# Macro_Pad.net
KiCad netlist of a schematic drawn in EasyEDA Pro
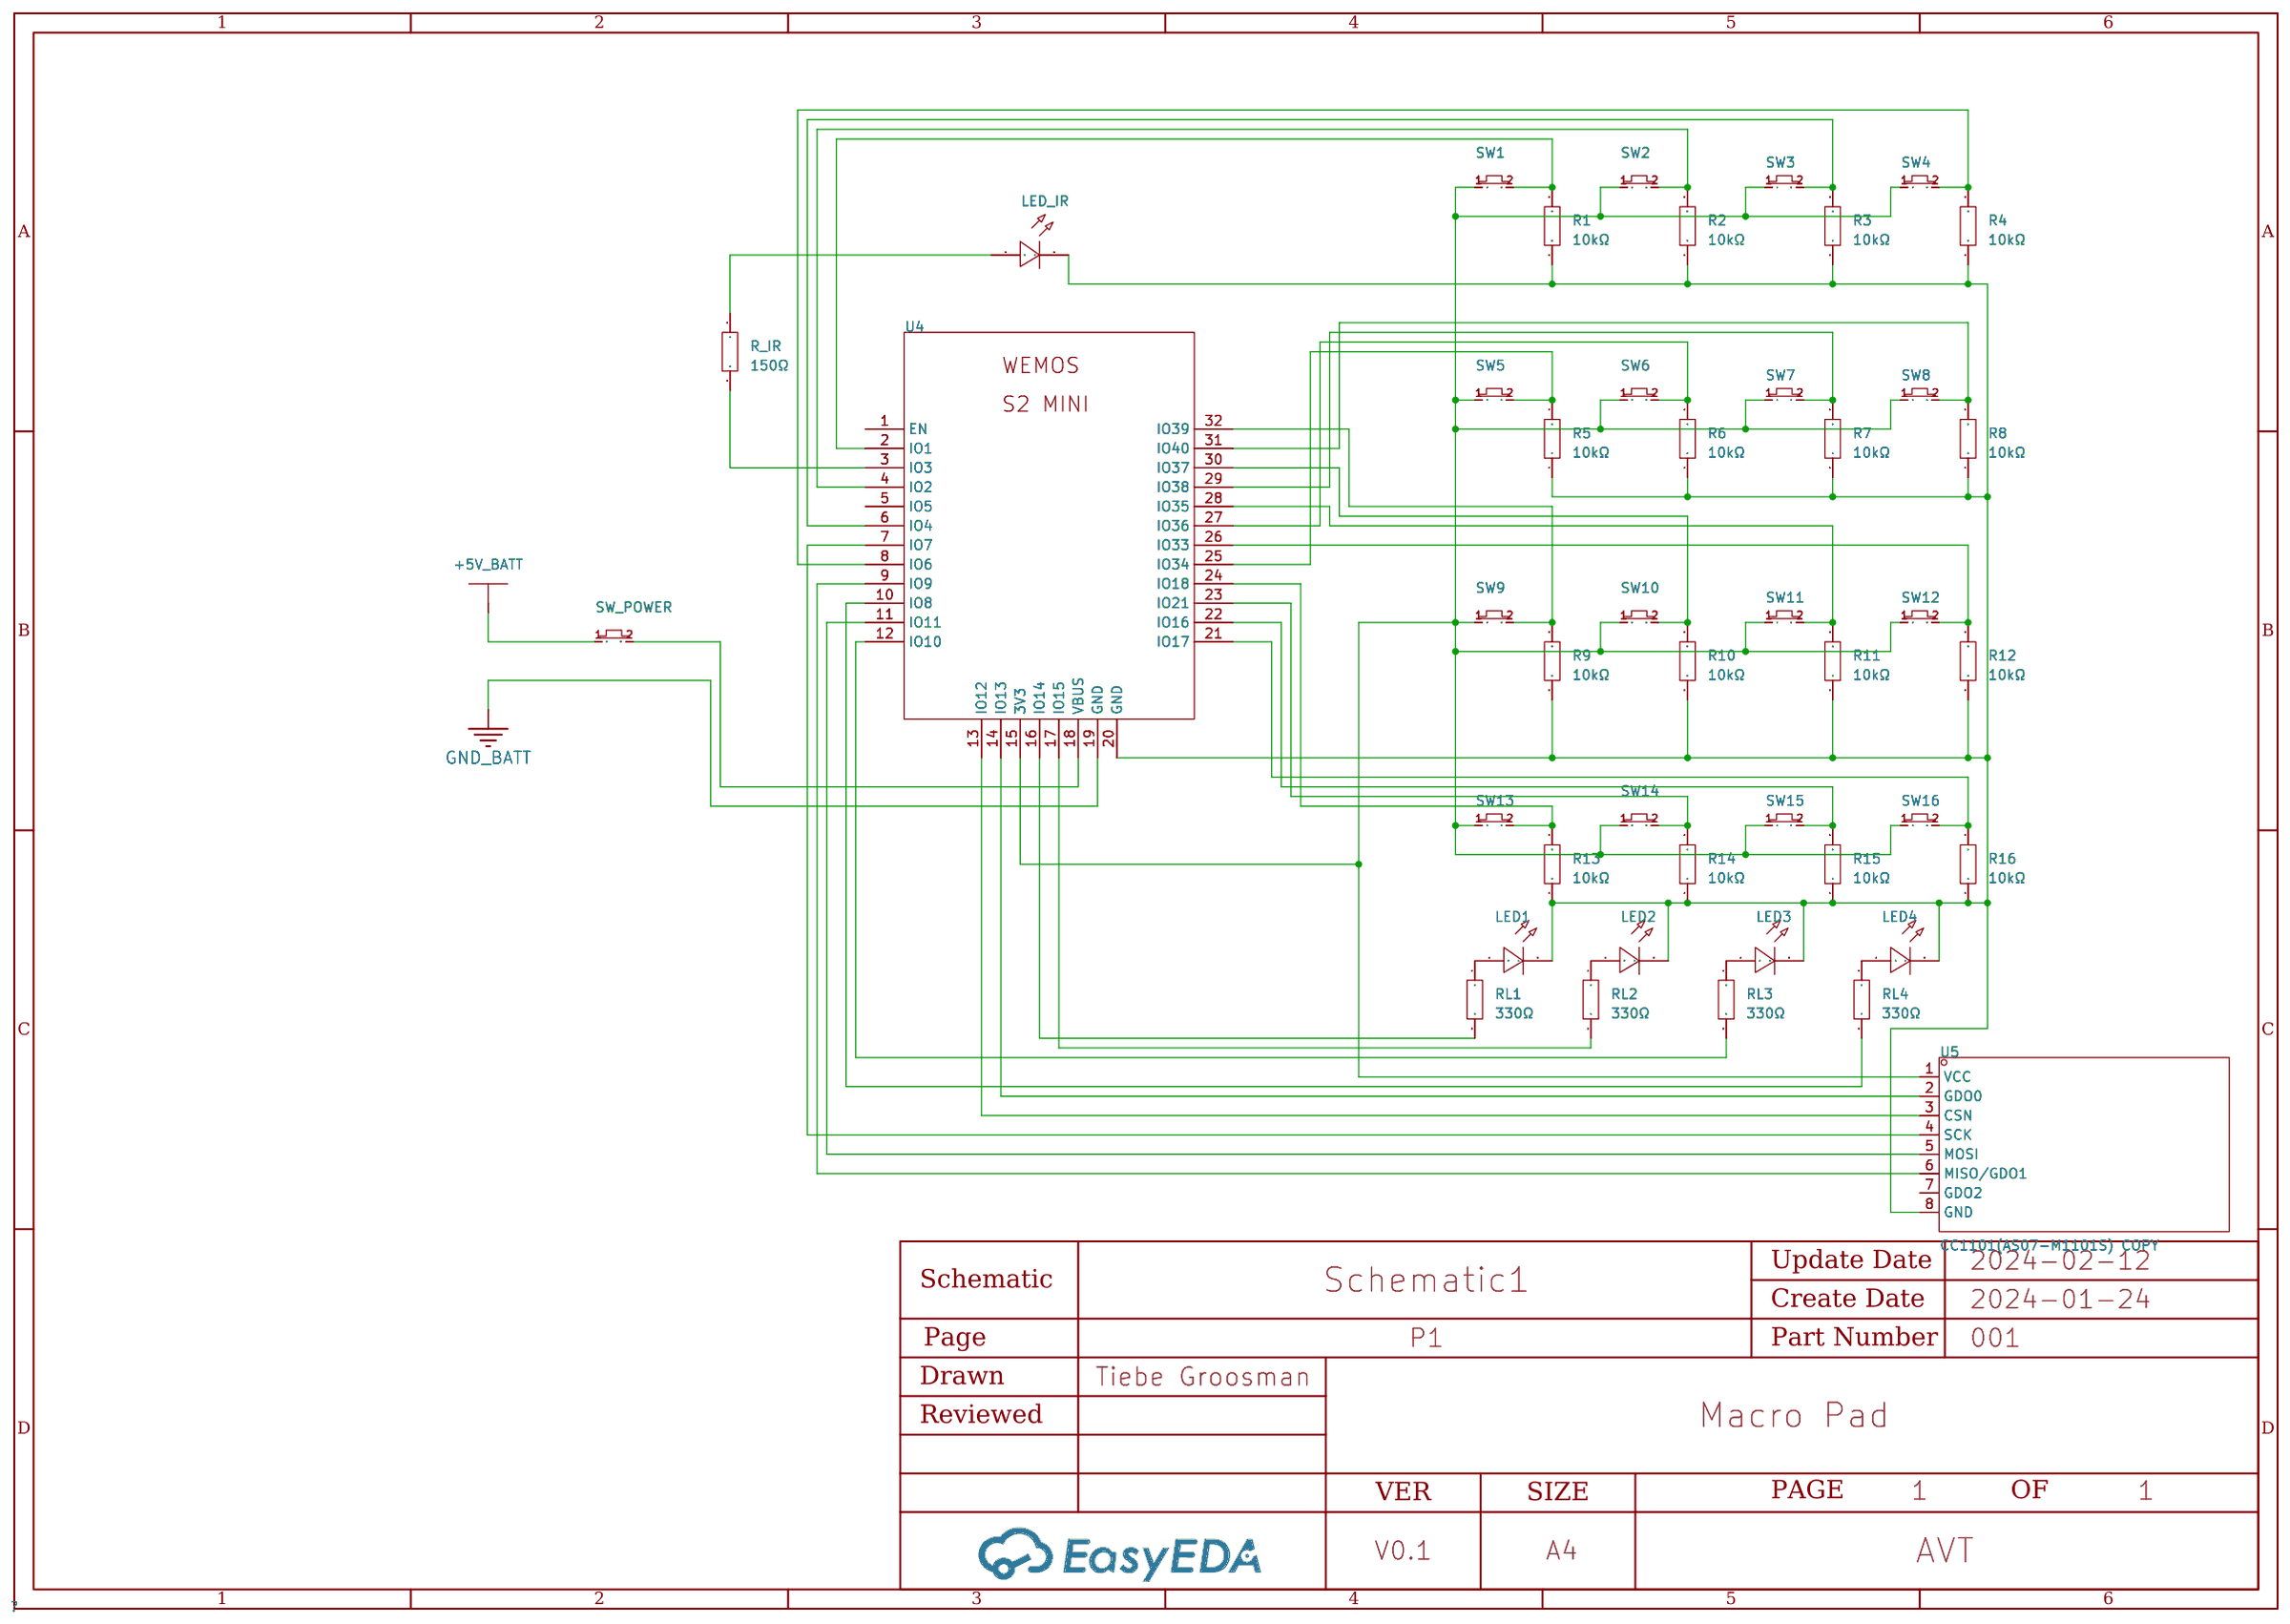
[diagram p0: schematic sheet]

(export (version "E")
  (design (tool "Eeschema 10.0.6"))
  (components
    (comp (ref "LED1")
      (value "~")
      (footprint "easyedapro:LED-TH_BD3.0-P2.54-FD")
      (libsource (lib "easyedapro") (part "LED_TH-R"))
    )
    (comp (ref "LED2")
      (value "~")
      (footprint "easyedapro:LED-TH_BD3.0-P2.54-FD")
      (libsource (lib "easyedapro") (part "LED_TH-R"))
    )
    (comp (ref "LED3")
      (value "~")
      (footprint "easyedapro:LED-TH_BD3.0-P2.54-FD")
      (libsource (lib "easyedapro") (part "LED_TH-R"))
    )
    (comp (ref "LED4")
      (value "~")
      (footprint "easyedapro:LED-TH_BD3.0-P2.54-FD")
      (libsource (lib "easyedapro") (part "LED_TH-R"))
    )
    (comp (ref "LED_IR")
      (value "~")
      (footprint "easyedapro:LED-TH_BD3.0-P2.54-FD")
      (libsource (lib "easyedapro") (part "LED_TH-R"))
    )
    (comp (ref "R1")
      (value "10kΩ")
      (footprint "easyedapro:R0201")
      (libsource (lib "easyedapro") (part "Res"))
    )
    (comp (ref "R2")
      (value "10kΩ")
      (footprint "easyedapro:R0201")
      (libsource (lib "easyedapro") (part "Res"))
    )
    (comp (ref "R3")
      (value "10kΩ")
      (footprint "easyedapro:R0201")
      (libsource (lib "easyedapro") (part "Res"))
    )
    (comp (ref "R4")
      (value "10kΩ")
      (footprint "easyedapro:R0201")
      (libsource (lib "easyedapro") (part "Res"))
    )
    (comp (ref "R5")
      (value "10kΩ")
      (footprint "easyedapro:R0201")
      (libsource (lib "easyedapro") (part "Res"))
    )
    (comp (ref "R6")
      (value "10kΩ")
      (footprint "easyedapro:R0201")
      (libsource (lib "easyedapro") (part "Res"))
    )
    (comp (ref "R7")
      (value "10kΩ")
      (footprint "easyedapro:R0201")
      (libsource (lib "easyedapro") (part "Res"))
    )
    (comp (ref "R8")
      (value "10kΩ")
      (footprint "easyedapro:R0201")
      (libsource (lib "easyedapro") (part "Res"))
    )
    (comp (ref "R9")
      (value "10kΩ")
      (footprint "easyedapro:R0201")
      (libsource (lib "easyedapro") (part "Res"))
    )
    (comp (ref "R10")
      (value "10kΩ")
      (footprint "easyedapro:R0201")
      (libsource (lib "easyedapro") (part "Res"))
    )
    (comp (ref "R11")
      (value "10kΩ")
      (footprint "easyedapro:R0201")
      (libsource (lib "easyedapro") (part "Res"))
    )
    (comp (ref "R12")
      (value "10kΩ")
      (footprint "easyedapro:R0201")
      (libsource (lib "easyedapro") (part "Res"))
    )
    (comp (ref "R13")
      (value "10kΩ")
      (footprint "easyedapro:R0201")
      (libsource (lib "easyedapro") (part "Res"))
    )
    (comp (ref "R14")
      (value "10kΩ")
      (footprint "easyedapro:R0201")
      (libsource (lib "easyedapro") (part "Res"))
    )
    (comp (ref "R15")
      (value "10kΩ")
      (footprint "easyedapro:R0201")
      (libsource (lib "easyedapro") (part "Res"))
    )
    (comp (ref "R16")
      (value "10kΩ")
      (footprint "easyedapro:R0201")
      (libsource (lib "easyedapro") (part "Res"))
    )
    (comp (ref "RL1")
      (value "330Ω")
      (footprint "easyedapro:R0201")
      (libsource (lib "easyedapro") (part "Res"))
    )
    (comp (ref "RL2")
      (value "330Ω")
      (footprint "easyedapro:R0201")
      (libsource (lib "easyedapro") (part "Res"))
    )
    (comp (ref "RL3")
      (value "330Ω")
      (footprint "easyedapro:R0201")
      (libsource (lib "easyedapro") (part "Res"))
    )
    (comp (ref "RL4")
      (value "330Ω")
      (footprint "easyedapro:R0201")
      (libsource (lib "easyedapro") (part "Res"))
    )
    (comp (ref "R_IR")
      (value "150Ω")
      (footprint "easyedapro:R0201")
      (libsource (lib "easyedapro") (part "Res"))
    )
    (comp (ref "SW1")
      (value "BUTTON-2PIN COPY")
      (footprint "easyedapro:BUTTON-2PIN")
      (fields
        (field (name "Manufacturer Part") "Switch,6*6*6Plastic head,260G, 0.25mm,Straight line")
        (field (name "Manufacturer") "BBJ")
      )
      (libsource (lib "easyedapro") (part "BUTTON-2PIN COPY"))
    )
    (comp (ref "SW2")
      (value "BUTTON-2PIN COPY")
      (footprint "easyedapro:BUTTON-2PIN")
      (fields
        (field (name "Manufacturer Part") "Switch,6*6*6Plastic head,260G, 0.25mm,Straight line")
        (field (name "Manufacturer") "BBJ")
      )
      (libsource (lib "easyedapro") (part "BUTTON-2PIN COPY"))
    )
    (comp (ref "SW3")
      (value "BUTTON-2PIN COPY")
      (footprint "easyedapro:BUTTON-2PIN")
      (fields
        (field (name "Manufacturer Part") "Switch,6*6*6Plastic head,260G, 0.25mm,Straight line")
        (field (name "Manufacturer") "BBJ")
      )
      (libsource (lib "easyedapro") (part "BUTTON-2PIN COPY"))
    )
    (comp (ref "SW4")
      (value "BUTTON-2PIN COPY")
      (footprint "easyedapro:BUTTON-2PIN")
      (fields
        (field (name "Manufacturer Part") "Switch,6*6*6Plastic head,260G, 0.25mm,Straight line")
        (field (name "Manufacturer") "BBJ")
      )
      (libsource (lib "easyedapro") (part "BUTTON-2PIN COPY"))
    )
    (comp (ref "SW5")
      (value "BUTTON-2PIN COPY")
      (footprint "easyedapro:BUTTON-2PIN")
      (fields
        (field (name "Manufacturer Part") "Switch,6*6*6Plastic head,260G, 0.25mm,Straight line")
        (field (name "Manufacturer") "BBJ")
      )
      (libsource (lib "easyedapro") (part "BUTTON-2PIN COPY"))
    )
    (comp (ref "SW6")
      (value "BUTTON-2PIN COPY")
      (footprint "easyedapro:BUTTON-2PIN")
      (fields
        (field (name "Manufacturer Part") "Switch,6*6*6Plastic head,260G, 0.25mm,Straight line")
        (field (name "Manufacturer") "BBJ")
      )
      (libsource (lib "easyedapro") (part "BUTTON-2PIN COPY"))
    )
    (comp (ref "SW7")
      (value "BUTTON-2PIN COPY")
      (footprint "easyedapro:BUTTON-2PIN")
      (fields
        (field (name "Manufacturer Part") "Switch,6*6*6Plastic head,260G, 0.25mm,Straight line")
        (field (name "Manufacturer") "BBJ")
      )
      (libsource (lib "easyedapro") (part "BUTTON-2PIN COPY"))
    )
    (comp (ref "SW8")
      (value "BUTTON-2PIN COPY")
      (footprint "easyedapro:BUTTON-2PIN")
      (fields
        (field (name "Manufacturer Part") "Switch,6*6*6Plastic head,260G, 0.25mm,Straight line")
        (field (name "Manufacturer") "BBJ")
      )
      (libsource (lib "easyedapro") (part "BUTTON-2PIN COPY"))
    )
    (comp (ref "SW9")
      (value "BUTTON-2PIN COPY")
      (footprint "easyedapro:BUTTON-2PIN")
      (fields
        (field (name "Manufacturer Part") "Switch,6*6*6Plastic head,260G, 0.25mm,Straight line")
        (field (name "Manufacturer") "BBJ")
      )
      (libsource (lib "easyedapro") (part "BUTTON-2PIN COPY"))
    )
    (comp (ref "SW10")
      (value "BUTTON-2PIN COPY")
      (footprint "easyedapro:BUTTON-2PIN")
      (fields
        (field (name "Manufacturer Part") "Switch,6*6*6Plastic head,260G, 0.25mm,Straight line")
        (field (name "Manufacturer") "BBJ")
      )
      (libsource (lib "easyedapro") (part "BUTTON-2PIN COPY"))
    )
    (comp (ref "SW11")
      (value "BUTTON-2PIN COPY")
      (footprint "easyedapro:BUTTON-2PIN")
      (fields
        (field (name "Manufacturer Part") "Switch,6*6*6Plastic head,260G, 0.25mm,Straight line")
        (field (name "Manufacturer") "BBJ")
      )
      (libsource (lib "easyedapro") (part "BUTTON-2PIN COPY"))
    )
    (comp (ref "SW12")
      (value "BUTTON-2PIN COPY")
      (footprint "easyedapro:BUTTON-2PIN")
      (fields
        (field (name "Manufacturer Part") "Switch,6*6*6Plastic head,260G, 0.25mm,Straight line")
        (field (name "Manufacturer") "BBJ")
      )
      (libsource (lib "easyedapro") (part "BUTTON-2PIN COPY"))
    )
    (comp (ref "SW13")
      (value "BUTTON-2PIN COPY")
      (footprint "easyedapro:BUTTON-2PIN")
      (fields
        (field (name "Manufacturer Part") "Switch,6*6*6Plastic head,260G, 0.25mm,Straight line")
        (field (name "Manufacturer") "BBJ")
      )
      (libsource (lib "easyedapro") (part "BUTTON-2PIN COPY"))
    )
    (comp (ref "SW14")
      (value "BUTTON-2PIN COPY")
      (footprint "easyedapro:BUTTON-2PIN")
      (fields
        (field (name "Manufacturer Part") "Switch,6*6*6Plastic head,260G, 0.25mm,Straight line")
        (field (name "Manufacturer") "BBJ")
      )
      (libsource (lib "easyedapro") (part "BUTTON-2PIN COPY"))
    )
    (comp (ref "SW15")
      (value "BUTTON-2PIN COPY")
      (footprint "easyedapro:BUTTON-2PIN")
      (fields
        (field (name "Manufacturer Part") "Switch,6*6*6Plastic head,260G, 0.25mm,Straight line")
        (field (name "Manufacturer") "BBJ")
      )
      (libsource (lib "easyedapro") (part "BUTTON-2PIN COPY"))
    )
    (comp (ref "SW16")
      (value "BUTTON-2PIN COPY")
      (footprint "easyedapro:BUTTON-2PIN")
      (fields
        (field (name "Manufacturer Part") "Switch,6*6*6Plastic head,260G, 0.25mm,Straight line")
        (field (name "Manufacturer") "BBJ")
      )
      (libsource (lib "easyedapro") (part "BUTTON-2PIN COPY"))
    )
    (comp (ref "SW_POWER")
      (value "BUTTON-2PIN COPY")
      (footprint "easyedapro:BUTTON-2PIN")
      (fields
        (field (name "Manufacturer Part") "Switch,6*6*6Plastic head,260G, 0.25mm,Straight line")
        (field (name "Manufacturer") "BBJ")
      )
      (libsource (lib "easyedapro") (part "BUTTON-2PIN COPY"))
    )
    (comp (ref "U4")
      (value "WEMOS S2 MINI COPY")
      (footprint "easyedapro:WEMOS-S2-MINI")
      (fields (field (name "Manufacturer Part") "Wemos") (field (name "Manufacturer") "WEMOS"))
      (libsource (lib "easyedapro") (part "WEMOS S2 MINI COPY"))
    )
    (comp (ref "U5")
      (value "CC1101(AS07-M1101S) COPY")
      (footprint "easyedapro:CC1101(AS07-M1101S)")
      (libsource (lib "easyedapro") (part "CC1101(AS07-M1101S) COPY"))
    )
  )
  (nets
    (net (code "1") (name "+5V_BATT") (class "Default")
      (node (ref "SW_POWER") (pin "1") (pinfunction "1_1") (pintype "input"))
    )
    (net (code "2") (name "GND_BATT") (class "Default")
      (node (ref "U4") (pin "19") (pinfunction "GND_19") (pintype "unspecified"))
    )
    (net (code "3") (name "Net-(LED1-A)") (class "Default")
      (node (ref "LED1") (pin "2") (pinfunction "A_2") (pintype "input"))
      (node (ref "LED2") (pin "2") (pinfunction "A_2") (pintype "input"))
      (node (ref "LED3") (pin "2") (pinfunction "A_2") (pintype "input"))
      (node (ref "LED4") (pin "2") (pinfunction "A_2") (pintype "input"))
      (node (ref "LED_IR") (pin "2") (pinfunction "A_2") (pintype "input"))
      (node (ref "R1") (pin "1") (pinfunction "1_1") (pintype "input"))
      (node (ref "R10") (pin "1") (pinfunction "1_1") (pintype "input"))
      (node (ref "R11") (pin "1") (pinfunction "1_1") (pintype "input"))
      (node (ref "R12") (pin "1") (pinfunction "1_1") (pintype "input"))
      (node (ref "R13") (pin "1") (pinfunction "1_1") (pintype "input"))
      (node (ref "R14") (pin "1") (pinfunction "1_1") (pintype "input"))
      (node (ref "R15") (pin "1") (pinfunction "1_1") (pintype "input"))
      (node (ref "R16") (pin "1") (pinfunction "1_1") (pintype "input"))
      (node (ref "R2") (pin "1") (pinfunction "1_1") (pintype "input"))
      (node (ref "R3") (pin "1") (pinfunction "1_1") (pintype "input"))
      (node (ref "R4") (pin "1") (pinfunction "1_1") (pintype "input"))
      (node (ref "R5") (pin "1") (pinfunction "1_1") (pintype "input"))
      (node (ref "R6") (pin "1") (pinfunction "1_1") (pintype "input"))
      (node (ref "R7") (pin "1") (pinfunction "1_1") (pintype "input"))
      (node (ref "R8") (pin "1") (pinfunction "1_1") (pintype "input"))
      (node (ref "R9") (pin "1") (pinfunction "1_1") (pintype "input"))
      (node (ref "U4") (pin "20") (pinfunction "GND_20") (pintype "unspecified"))
      (node (ref "U5") (pin "8") (pinfunction "GND_8") (pintype "unspecified"))
    )
    (net (code "4") (name "Net-(LED1-C)") (class "Default")
      (node (ref "LED1") (pin "1") (pinfunction "C_1") (pintype "input"))
      (node (ref "RL1") (pin "1") (pinfunction "1_1") (pintype "input"))
    )
    (net (code "5") (name "Net-(LED2-C)") (class "Default")
      (node (ref "LED2") (pin "1") (pinfunction "C_1") (pintype "input"))
      (node (ref "RL2") (pin "1") (pinfunction "1_1") (pintype "input"))
    )
    (net (code "6") (name "Net-(LED3-C)") (class "Default")
      (node (ref "LED3") (pin "1") (pinfunction "C_1") (pintype "input"))
      (node (ref "RL3") (pin "1") (pinfunction "1_1") (pintype "input"))
    )
    (net (code "7") (name "Net-(LED4-C)") (class "Default")
      (node (ref "LED4") (pin "1") (pinfunction "C_1") (pintype "input"))
      (node (ref "RL4") (pin "1") (pinfunction "1_1") (pintype "input"))
    )
    (net (code "8") (name "Net-(LED_IR-C)") (class "Default")
      (node (ref "LED_IR") (pin "1") (pinfunction "C_1") (pintype "input"))
      (node (ref "R_IR") (pin "1") (pinfunction "1_1") (pintype "input"))
    )
    (net (code "9") (name "Net-(SW1-3)") (class "Default")
      (node (ref "R1") (pin "2") (pinfunction "2_2") (pintype "input"))
      (node (ref "SW1") (pin "2") (pinfunction "3_2") (pintype "input"))
      (node (ref "U4") (pin "2") (pinfunction "IO1_2") (pintype "bidirectional"))
    )
    (net (code "10") (name "Net-(SW2-3)") (class "Default")
      (node (ref "R2") (pin "2") (pinfunction "2_2") (pintype "input"))
      (node (ref "SW2") (pin "2") (pinfunction "3_2") (pintype "input"))
      (node (ref "U4") (pin "4") (pinfunction "IO2_4") (pintype "bidirectional"))
    )
    (net (code "11") (name "Net-(SW3-3)") (class "Default")
      (node (ref "R3") (pin "2") (pinfunction "2_2") (pintype "input"))
      (node (ref "SW3") (pin "2") (pinfunction "3_2") (pintype "input"))
      (node (ref "U4") (pin "6") (pinfunction "IO4_6") (pintype "bidirectional"))
    )
    (net (code "12") (name "Net-(SW4-3)") (class "Default")
      (node (ref "R4") (pin "2") (pinfunction "2_2") (pintype "input"))
      (node (ref "SW4") (pin "2") (pinfunction "3_2") (pintype "input"))
      (node (ref "U4") (pin "8") (pinfunction "IO6_8") (pintype "bidirectional"))
    )
    (net (code "13") (name "Net-(SW5-3)") (class "Default")
      (node (ref "R5") (pin "2") (pinfunction "2_2") (pintype "input"))
      (node (ref "SW5") (pin "2") (pinfunction "3_2") (pintype "input"))
      (node (ref "U4") (pin "25") (pinfunction "IO34_25") (pintype "unspecified"))
    )
    (net (code "14") (name "Net-(SW6-3)") (class "Default")
      (node (ref "R6") (pin "2") (pinfunction "2_2") (pintype "input"))
      (node (ref "SW6") (pin "2") (pinfunction "3_2") (pintype "input"))
      (node (ref "U4") (pin "27") (pinfunction "IO36_27") (pintype "unspecified"))
    )
    (net (code "15") (name "Net-(SW7-3)") (class "Default")
      (node (ref "R7") (pin "2") (pinfunction "2_2") (pintype "input"))
      (node (ref "SW7") (pin "2") (pinfunction "3_2") (pintype "input"))
      (node (ref "U4") (pin "29") (pinfunction "IO38_29") (pintype "unspecified"))
    )
    (net (code "16") (name "Net-(SW8-3)") (class "Default")
      (node (ref "R8") (pin "2") (pinfunction "2_2") (pintype "input"))
      (node (ref "SW8") (pin "2") (pinfunction "3_2") (pintype "input"))
      (node (ref "U4") (pin "31") (pinfunction "IO40_31") (pintype "unspecified"))
    )
    (net (code "17") (name "Net-(SW9-3)") (class "Default")
      (node (ref "R9") (pin "2") (pinfunction "2_2") (pintype "input"))
      (node (ref "SW9") (pin "2") (pinfunction "3_2") (pintype "input"))
      (node (ref "U4") (pin "32") (pinfunction "IO39_32") (pintype "unspecified"))
    )
    (net (code "18") (name "Net-(SW10-3)") (class "Default")
      (node (ref "R10") (pin "2") (pinfunction "2_2") (pintype "input"))
      (node (ref "SW10") (pin "2") (pinfunction "3_2") (pintype "input"))
      (node (ref "U4") (pin "30") (pinfunction "IO37_30") (pintype "unspecified"))
    )
    (net (code "19") (name "Net-(SW11-3)") (class "Default")
      (node (ref "R11") (pin "2") (pinfunction "2_2") (pintype "input"))
      (node (ref "SW11") (pin "2") (pinfunction "3_2") (pintype "input"))
      (node (ref "U4") (pin "28") (pinfunction "IO35_28") (pintype "unspecified"))
    )
    (net (code "20") (name "Net-(SW12-3)") (class "Default")
      (node (ref "R12") (pin "2") (pinfunction "2_2") (pintype "input"))
      (node (ref "SW12") (pin "2") (pinfunction "3_2") (pintype "input"))
      (node (ref "U4") (pin "26") (pinfunction "IO33_26") (pintype "unspecified"))
    )
    (net (code "21") (name "Net-(SW13-3)") (class "Default")
      (node (ref "R13") (pin "2") (pinfunction "2_2") (pintype "input"))
      (node (ref "SW13") (pin "2") (pinfunction "3_2") (pintype "input"))
      (node (ref "U4") (pin "24") (pinfunction "IO18_24") (pintype "unspecified"))
    )
    (net (code "22") (name "Net-(SW14-3)") (class "Default")
      (node (ref "R14") (pin "2") (pinfunction "2_2") (pintype "input"))
      (node (ref "SW14") (pin "2") (pinfunction "3_2") (pintype "input"))
      (node (ref "U4") (pin "23") (pinfunction "IO21_23") (pintype "unspecified"))
    )
    (net (code "23") (name "Net-(SW15-3)") (class "Default")
      (node (ref "R15") (pin "2") (pinfunction "2_2") (pintype "input"))
      (node (ref "SW15") (pin "2") (pinfunction "3_2") (pintype "input"))
      (node (ref "U4") (pin "22") (pinfunction "IO16_22") (pintype "unspecified"))
    )
    (net (code "24") (name "Net-(SW16-3)") (class "Default")
      (node (ref "R16") (pin "2") (pinfunction "2_2") (pintype "input"))
      (node (ref "SW16") (pin "2") (pinfunction "3_2") (pintype "input"))
      (node (ref "U4") (pin "21") (pinfunction "IO17_21") (pintype "unspecified"))
    )
    (net (code "25") (name "Net-(SW_POWER-3)") (class "Default")
      (node (ref "SW_POWER") (pin "2") (pinfunction "3_2") (pintype "input"))
      (node (ref "U4") (pin "18") (pinfunction "VBUS_18") (pintype "bidirectional"))
    )
    (net (code "26") (name "Net-(U4-3V3)") (class "Default")
      (node (ref "SW1") (pin "1") (pinfunction "1_1") (pintype "input"))
      (node (ref "SW10") (pin "1") (pinfunction "1_1") (pintype "input"))
      (node (ref "SW11") (pin "1") (pinfunction "1_1") (pintype "input"))
      (node (ref "SW12") (pin "1") (pinfunction "1_1") (pintype "input"))
      (node (ref "SW13") (pin "1") (pinfunction "1_1") (pintype "input"))
      (node (ref "SW14") (pin "1") (pinfunction "1_1") (pintype "input"))
      (node (ref "SW15") (pin "1") (pinfunction "1_1") (pintype "input"))
      (node (ref "SW16") (pin "1") (pinfunction "1_1") (pintype "input"))
      (node (ref "SW2") (pin "1") (pinfunction "1_1") (pintype "input"))
      (node (ref "SW3") (pin "1") (pinfunction "1_1") (pintype "input"))
      (node (ref "SW4") (pin "1") (pinfunction "1_1") (pintype "input"))
      (node (ref "SW5") (pin "1") (pinfunction "1_1") (pintype "input"))
      (node (ref "SW6") (pin "1") (pinfunction "1_1") (pintype "input"))
      (node (ref "SW7") (pin "1") (pinfunction "1_1") (pintype "input"))
      (node (ref "SW8") (pin "1") (pinfunction "1_1") (pintype "input"))
      (node (ref "SW9") (pin "1") (pinfunction "1_1") (pintype "input"))
      (node (ref "U4") (pin "15") (pinfunction "3V3_15") (pintype "unspecified"))
      (node (ref "U5") (pin "1") (pinfunction "VCC_1") (pintype "unspecified"))
    )
    (net (code "27") (name "Net-(U4-IO3)") (class "Default")
      (node (ref "R_IR") (pin "2") (pinfunction "2_2") (pintype "input"))
      (node (ref "U4") (pin "3") (pinfunction "IO3_3") (pintype "bidirectional"))
    )
    (net (code "28") (name "Net-(U4-IO7)") (class "Default")
      (node (ref "U4") (pin "7") (pinfunction "IO7_7") (pintype "bidirectional"))
      (node (ref "U5") (pin "4") (pinfunction "SCK_4") (pintype "unspecified"))
    )
    (net (code "29") (name "Net-(U4-IO8)") (class "Default")
      (node (ref "RL4") (pin "2") (pinfunction "2_2") (pintype "input"))
      (node (ref "U4") (pin "10") (pinfunction "IO8_10") (pintype "bidirectional"))
    )
    (net (code "30") (name "Net-(U4-IO9)") (class "Default")
      (node (ref "U4") (pin "9") (pinfunction "IO9_9") (pintype "bidirectional"))
      (node (ref "U5") (pin "6") (pinfunction "MISO/GDO1_6") (pintype "unspecified"))
    )
    (net (code "31") (name "Net-(U4-IO10)") (class "Default")
      (node (ref "RL3") (pin "2") (pinfunction "2_2") (pintype "input"))
      (node (ref "U4") (pin "12") (pinfunction "IO10_12") (pintype "bidirectional"))
    )
    (net (code "32") (name "Net-(U4-IO11)") (class "Default")
      (node (ref "U4") (pin "11") (pinfunction "IO11_11") (pintype "bidirectional"))
      (node (ref "U5") (pin "5") (pinfunction "MOSI_5") (pintype "unspecified"))
    )
    (net (code "33") (name "Net-(U4-IO12)") (class "Default")
      (node (ref "U4") (pin "13") (pinfunction "IO12_13") (pintype "bidirectional"))
      (node (ref "U5") (pin "3") (pinfunction "CSN_3") (pintype "unspecified"))
    )
    (net (code "34") (name "Net-(U4-IO13)") (class "Default")
      (node (ref "U4") (pin "14") (pinfunction "IO13_14") (pintype "bidirectional"))
      (node (ref "U5") (pin "2") (pinfunction "GDO0_2") (pintype "unspecified"))
    )
    (net (code "35") (name "Net-(U4-IO14)") (class "Default")
      (node (ref "RL1") (pin "2") (pinfunction "2_2") (pintype "input"))
      (node (ref "U4") (pin "16") (pinfunction "IO14_16") (pintype "bidirectional"))
    )
    (net (code "36") (name "Net-(U4-IO15)") (class "Default")
      (node (ref "RL2") (pin "2") (pinfunction "2_2") (pintype "input"))
      (node (ref "U4") (pin "17") (pinfunction "IO15_17") (pintype "bidirectional"))
    )
    (net (code "37") (name "unconnected-(U4-EN-Pad1)") (class "Default")
      (node (ref "U4") (pin "1") (pinfunction "EN_1") (pintype "input"))
    )
    (net (code "38") (name "unconnected-(U4-IO5-Pad5)") (class "Default")
      (node (ref "U4") (pin "5") (pinfunction "IO5_5") (pintype "bidirectional"))
    )
    (net (code "39") (name "unconnected-(U5-GDO2-Pad7)") (class "Default")
      (node (ref "U5") (pin "7") (pinfunction "GDO2_7") (pintype "unspecified"))
    )
  )
)
